# schematic.net
KiCad netlist of a schematic drawn in Altium Designer
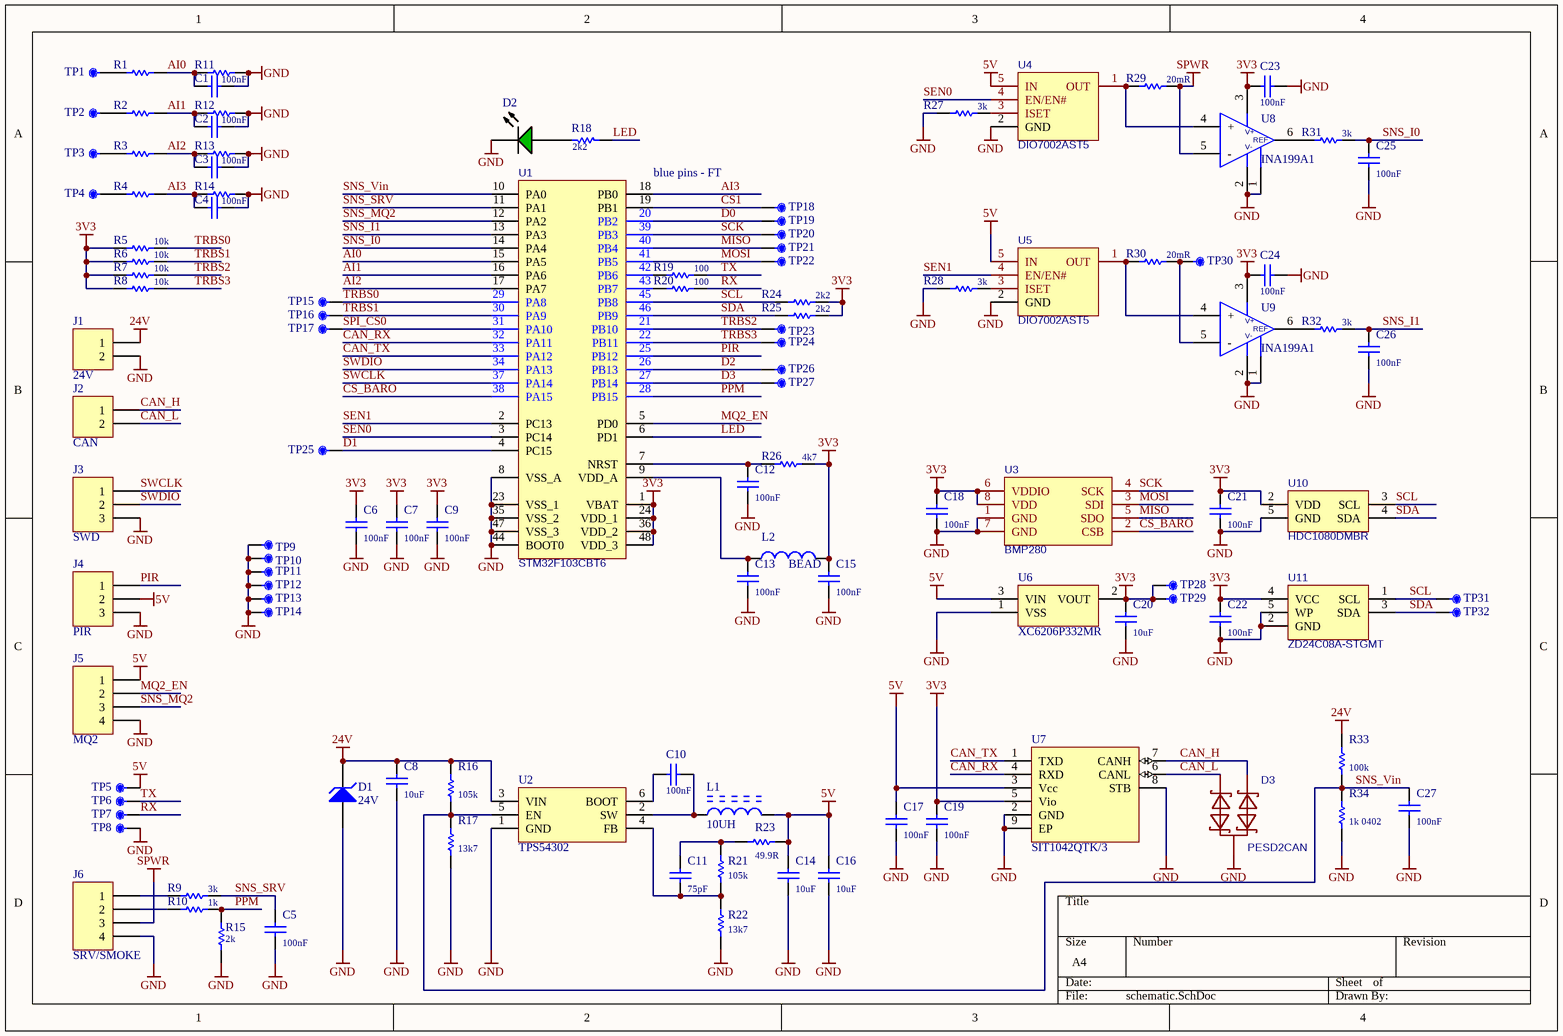
[diagram p0: schematic.SchDoc]

(export (version "E")
  (design (tool "Eeschema 10.0.6"))
  (components
    (comp (ref "C1")
      (value "100nF")
      (footprint "C0402")
      (description "100nF 50V 0402")
      (fields (field (name "LCSC PART NUMBER") "C110251"))
      (libsource (lib "Miscellaneous Devices") (part "CAP"))
    )
    (comp (ref "C2")
      (value "100nF")
      (footprint "C0402")
      (description "100nF 50V 0402")
      (fields (field (name "LCSC PART NUMBER") "C110251"))
      (libsource (lib "Miscellaneous Devices") (part "CAP"))
    )
    (comp (ref "C3")
      (value "100nF")
      (footprint "C0402")
      (description "100nF 50V 0402")
      (fields (field (name "LCSC PART NUMBER") "C110251"))
      (libsource (lib "Miscellaneous Devices") (part "CAP"))
    )
    (comp (ref "C4")
      (value "100nF")
      (footprint "C0402")
      (description "100nF 50V 0402")
      (fields (field (name "LCSC PART NUMBER") "C110251"))
      (libsource (lib "Miscellaneous Devices") (part "CAP"))
    )
    (comp (ref "C5")
      (value "100nF")
      (footprint "C0402")
      (description "100nF 50V 0402")
      (fields (field (name "LCSC PART NUMBER") "C110251"))
      (libsource (lib "Miscellaneous Devices") (part "CAP"))
    )
    (comp (ref "C6")
      (value "100nF")
      (footprint "C0402")
      (description "100nF 50V 0402")
      (fields (field (name "LCSC PART NUMBER") "C110251"))
      (libsource (lib "Miscellaneous Devices") (part "CAP"))
    )
    (comp (ref "C7")
      (value "100nF")
      (footprint "C0402")
      (description "100nF 50V 0402")
      (fields (field (name "LCSC PART NUMBER") "C110251"))
      (libsource (lib "Miscellaneous Devices") (part "CAP"))
    )
    (comp (ref "C8")
      (value "10uF")
      (footprint "C1206")
      (description "10uf 50V 1206")
      (fields (field (name "LCSC PART NUMBER") "C89632"))
      (libsource (lib "Miscellaneous Devices") (part "CAP"))
    )
    (comp (ref "C9")
      (value "100nF")
      (footprint "C0402")
      (description "100nF 50V 0402")
      (fields (field (name "LCSC PART NUMBER") "C110251"))
      (libsource (lib "Miscellaneous Devices") (part "CAP"))
    )
    (comp (ref "C10")
      (value "100nF")
      (footprint "C0402")
      (description "100nF 50V 0402")
      (fields (field (name "LCSC PART NUMBER") "C110251"))
      (libsource (lib "Miscellaneous Devices") (part "CAP"))
    )
    (comp (ref "C11")
      (value "75pF")
      (footprint "C0402")
      (description "75pF 50V 0402")
      (fields (field (name "LCSC PART NUMBER") "C107010"))
      (libsource (lib "Miscellaneous Devices") (part "CAP"))
    )
    (comp (ref "C12")
      (value "100nF")
      (footprint "C0402")
      (description "100nF 50V 0402")
      (fields (field (name "LCSC PART NUMBER") "C110251"))
      (libsource (lib "Miscellaneous Devices") (part "CAP"))
    )
    (comp (ref "C13")
      (value "100nF")
      (footprint "C0402")
      (description "100nF 50V 0402")
      (fields (field (name "LCSC PART NUMBER") "C110251"))
      (libsource (lib "Miscellaneous Devices") (part "CAP"))
    )
    (comp (ref "C14")
      (value "10uF")
      (footprint "C1206")
      (description "10uf 50V 1206")
      (fields (field (name "LCSC PART NUMBER") "C89632"))
      (libsource (lib "Miscellaneous Devices") (part "CAP"))
    )
    (comp (ref "C15")
      (value "100nF")
      (footprint "C0402")
      (description "100nF 50V 0402")
      (fields (field (name "LCSC PART NUMBER") "C110251"))
      (libsource (lib "Miscellaneous Devices") (part "CAP"))
    )
    (comp (ref "C16")
      (value "10uF")
      (footprint "C1206")
      (description "10uf 50V 1206")
      (fields (field (name "LCSC PART NUMBER") "C89632"))
      (libsource (lib "Miscellaneous Devices") (part "CAP"))
    )
    (comp (ref "C17")
      (value "100nF")
      (footprint "C0402")
      (description "100nF 50V 0402")
      (fields (field (name "LCSC PART NUMBER") "C110251"))
      (libsource (lib "Miscellaneous Devices") (part "CAP"))
    )
    (comp (ref "C18")
      (value "100nF")
      (footprint "C0402")
      (description "100nF 50V 0402")
      (fields (field (name "LCSC PART NUMBER") "C110251"))
      (libsource (lib "Miscellaneous Devices") (part "CAP"))
    )
    (comp (ref "C19")
      (value "100nF")
      (footprint "C0402")
      (description "100nF 50V 0402")
      (fields (field (name "LCSC PART NUMBER") "C110251"))
      (libsource (lib "Miscellaneous Devices") (part "CAP"))
    )
    (comp (ref "C20")
      (value "10uF")
      (footprint "C1206")
      (description "10uf 50V 1206")
      (fields (field (name "LCSC PART NUMBER") "C89632"))
      (libsource (lib "Miscellaneous Devices") (part "CAP"))
    )
    (comp (ref "C21")
      (value "100nF")
      (footprint "C0402")
      (description "100nF 50V 0402")
      (fields (field (name "LCSC PART NUMBER") "C110251"))
      (libsource (lib "Miscellaneous Devices") (part "CAP"))
    )
    (comp (ref "C22")
      (value "100nF")
      (footprint "C0402")
      (description "100nF 50V 0402")
      (fields (field (name "LCSC PART NUMBER") "C110251"))
      (libsource (lib "Miscellaneous Devices") (part "CAP"))
    )
    (comp (ref "C23")
      (value "100nF")
      (footprint "C0402")
      (description "100nF 50V 0402")
      (fields (field (name "LCSC PART NUMBER") "C110251"))
      (libsource (lib "Miscellaneous Devices") (part "CAP"))
    )
    (comp (ref "C24")
      (value "100nF")
      (footprint "C0402")
      (description "100nF 50V 0402")
      (fields (field (name "LCSC PART NUMBER") "C110251"))
      (libsource (lib "Miscellaneous Devices") (part "CAP"))
    )
    (comp (ref "C25")
      (value "100nF")
      (footprint "C0402")
      (description "100nF 50V 0402")
      (fields (field (name "LCSC PART NUMBER") "C110251"))
      (libsource (lib "Miscellaneous Devices") (part "CAP"))
    )
    (comp (ref "C26")
      (value "100nF")
      (footprint "C0402")
      (description "100nF 50V 0402")
      (fields (field (name "LCSC PART NUMBER") "C110251"))
      (libsource (lib "Miscellaneous Devices") (part "CAP"))
    )
    (comp (ref "C27")
      (value "100nF")
      (footprint "C0402")
      (description "100nF 50V 0402")
      (fields (field (name "LCSC PART NUMBER") "C110251"))
      (libsource (lib "Miscellaneous Devices") (part "CAP"))
    )
    (comp (ref "D1")
      (value "24V")
      (footprint "SMB")
      (description "P6SMB24A")
      (fields (field (name "LCSC PART NUMBER") "C5155417"))
      (libsource (lib "Miscellaneous Devices") (part "SMCJ54A"))
    )
    (comp (ref "D2")
      (value "GRN")
      (footprint "LED-0603-GRN")
      (description "LED 0603 GRN")
      (fields (field (name "LCSC PART NUMBER") "C434446"))
      (libsource (lib "Miscellaneous Devices") (part "LED-0603-GREEN"))
    )
    (comp (ref "D3")
      (value "PESD2CAN")
      (footprint "SOT-23")
      (fields (field (name "LCSC PART NUMBER") "C5261081"))
      (libsource (lib "Miscellaneous Devices") (part "CDSOT23-SM712"))
    )
    (comp (ref "J1")
      (value "24V")
      (footprint "CONN_DG308-2.54-2P")
      (description "DG308-2.54-02P-14-00A(H)")
      (fields (field (name "LCSC PART NUMBER") "C699496"))
      (libsource (lib "Miscellaneous Devices") (part "CONN MOLEX HDR-M 1x4"))
    )
    (comp (ref "J2")
      (value "CAN")
      (footprint "CONN_DG308-2.54-2P")
      (description "DG308-2.54-02P-14-00A(H)")
      (fields (field (name "LCSC PART NUMBER") "C699496"))
      (libsource (lib "Miscellaneous Devices") (part "CONN MOLEX HDR-M 1x4"))
    )
    (comp (ref "J3")
      (value "SWD")
      (footprint "SWD")
      (libsource (lib "Miscellaneous Devices") (part "Header 3"))
    )
    (comp (ref "J4")
      (value "PIR")
      (footprint "CONN_MOLEX_532610371")
      (libsource (lib "Miscellaneous Devices") (part "Header 3"))
    )
    (comp (ref "J5")
      (value "MQ2")
      (footprint "CONN_MOLEX_532610471")
      (libsource (lib "Schlib1") (part "Header 3"))
    )
    (comp (ref "J6") (value "SRV/SMOKE") (footprint "HDR-1X4") (libsource (lib "Schlib1") (part "Header 3")))
    (comp (ref "L1")
      (value "10UH")
      (footprint "IND-SMD_L7.2-W6.6_GPSR07X0")
      (description "CYA0630-10UH")
      (fields (field (name "LCSC PART NUMBER") "C5189958"))
      (libsource (lib "Miscellaneous Devices") (part "SRN3015-100M"))
    )
    (comp (ref "L2")
      (value "BEAD")
      (footprint "L0402")
      (description "BEAD 0402")
      (fields (field (name "LCSC PART NUMBER") "C76883"))
      (libsource (lib "Miscellaneous Devices") (part "BLM18AG601SN1D"))
    )
    (comp (ref "R1")
      (value "10k")
      (footprint "R0402")
      (description "10k 0402")
      (fields (field (name "LCSC PART NUMBER") "C25744"))
      (libsource (lib "Miscellaneous Devices") (part "RES"))
    )
    (comp (ref "R2")
      (value "10k")
      (footprint "R0402")
      (description "10k 0402")
      (fields (field (name "LCSC PART NUMBER") "C25744"))
      (libsource (lib "Miscellaneous Devices") (part "RES"))
    )
    (comp (ref "R3")
      (value "10k")
      (footprint "R0402")
      (description "10k 0402")
      (fields (field (name "LCSC PART NUMBER") "C25744"))
      (libsource (lib "Miscellaneous Devices") (part "RES"))
    )
    (comp (ref "R4")
      (value "10k")
      (footprint "R0402")
      (description "10k 0402")
      (fields (field (name "LCSC PART NUMBER") "C25744"))
      (libsource (lib "Miscellaneous Devices") (part "RES"))
    )
    (comp (ref "R5")
      (value "10k")
      (footprint "R0402")
      (description "10k 0402")
      (fields (field (name "LCSC PART NUMBER") "C25744"))
      (libsource (lib "Miscellaneous Devices") (part "RES"))
    )
    (comp (ref "R6")
      (value "10k")
      (footprint "R0402")
      (description "10k 0402")
      (fields (field (name "LCSC PART NUMBER") "C25744"))
      (libsource (lib "Miscellaneous Devices") (part "RES"))
    )
    (comp (ref "R7")
      (value "10k")
      (footprint "R0402")
      (description "10k 0402")
      (fields (field (name "LCSC PART NUMBER") "C25744"))
      (libsource (lib "Miscellaneous Devices") (part "RES"))
    )
    (comp (ref "R8")
      (value "10k")
      (footprint "R0402")
      (description "10k 0402")
      (fields (field (name "LCSC PART NUMBER") "C25744"))
      (libsource (lib "Miscellaneous Devices") (part "RES"))
    )
    (comp (ref "R9")
      (value "3k")
      (footprint "R0402")
      (description "3k 0402")
      (fields (field (name "LCSC PART NUMBER") "C25784"))
      (libsource (lib "") (part "RES_1"))
    )
    (comp (ref "R10")
      (value "1k")
      (footprint "R0402")
      (description "1k 0402")
      (fields (field (name "LCSC PART NUMBER") "C11702"))
      (libsource (lib "Miscellaneous Devices") (part "RES"))
    )
    (comp (ref "R11")
      (value "20k")
      (footprint "R0402")
      (description "20k 0402")
      (fields (field (name "LCSC PART NUMBER") "C25765"))
      (libsource (lib "Miscellaneous Devices") (part "RES"))
    )
    (comp (ref "R12")
      (value "20k")
      (footprint "R0402")
      (description "20k 0402")
      (fields (field (name "LCSC PART NUMBER") "C25765"))
      (libsource (lib "Miscellaneous Devices") (part "RES"))
    )
    (comp (ref "R13")
      (value "20k")
      (footprint "R0402")
      (description "20k 0402")
      (fields (field (name "LCSC PART NUMBER") "C25765"))
      (libsource (lib "Miscellaneous Devices") (part "RES"))
    )
    (comp (ref "R14")
      (value "20k")
      (footprint "R0402")
      (description "20k 0402")
      (fields (field (name "LCSC PART NUMBER") "C25765"))
      (libsource (lib "Miscellaneous Devices") (part "RES"))
    )
    (comp (ref "R15")
      (value "2k")
      (footprint "R0402")
      (description "2k 0402")
      (fields (field (name "LCSC PART NUMBER") "C4109"))
      (libsource (lib "Miscellaneous Devices") (part "RES"))
    )
    (comp (ref "R16")
      (value "105k")
      (footprint "R0402")
      (description "105k 0402")
      (fields (field (name "LCSC PART NUMBER") "C170210"))
      (libsource (lib "Miscellaneous Devices") (part "RES"))
    )
    (comp (ref "R17")
      (value "13k7")
      (footprint "R0402")
      (description "13k7 0402")
      (fields (field (name "LCSC PART NUMBER") "C2933072"))
      (libsource (lib "Miscellaneous Devices") (part "RES"))
    )
    (comp (ref "R18")
      (value "2k2")
      (footprint "R0402")
      (description "2k 0402")
      (fields (field (name "LCSC PART NUMBER") "C4109"))
      (libsource (lib "Miscellaneous Devices") (part "RES"))
    )
    (comp (ref "R19")
      (value "100")
      (footprint "R0402")
      (description "100 0402")
      (fields (field (name "LCSC PART NUMBER") "C25076"))
      (libsource (lib "Miscellaneous Devices") (part "RES"))
    )
    (comp (ref "R20")
      (value "100")
      (footprint "R0402")
      (description "100 0402")
      (fields (field (name "LCSC PART NUMBER") "C25076"))
      (libsource (lib "Miscellaneous Devices") (part "RES"))
    )
    (comp (ref "R21")
      (value "105k")
      (footprint "R0402")
      (description "105k 0402")
      (fields (field (name "LCSC PART NUMBER") "C170210"))
      (libsource (lib "Miscellaneous Devices") (part "RES"))
    )
    (comp (ref "R22")
      (value "13k7")
      (footprint "R0402")
      (description "13k7 0402")
      (fields (field (name "LCSC PART NUMBER") "C2933072"))
      (libsource (lib "Miscellaneous Devices") (part "RES"))
    )
    (comp (ref "R23")
      (value "49.9R")
      (footprint "R0402")
      (description "49R9 0402")
      (fields (field (name "LCSC PART NUMBER") "C87044"))
      (libsource (lib "") (part "RES_2"))
    )
    (comp (ref "R24")
      (value "2k2")
      (footprint "R0402")
      (description "2k 0402")
      (fields (field (name "LCSC PART NUMBER") "C4109"))
      (libsource (lib "Miscellaneous Devices") (part "RES"))
    )
    (comp (ref "R25")
      (value "2k2")
      (footprint "R0402")
      (description "2k 0402")
      (fields (field (name "LCSC PART NUMBER") "C4109"))
      (libsource (lib "Miscellaneous Devices") (part "RES"))
    )
    (comp (ref "R26")
      (value "4k7")
      (footprint "R0402")
      (description "4k7 0402")
      (fields (field (name "LCSC PART NUMBER") "C25900"))
      (libsource (lib "Miscellaneous Devices") (part "RES"))
    )
    (comp (ref "R27")
      (value "3k")
      (footprint "R0402")
      (description "3k 0402")
      (fields (field (name "LCSC PART NUMBER") "C25784"))
      (libsource (lib "") (part "RES_1"))
    )
    (comp (ref "R28")
      (value "3k")
      (footprint "R0402")
      (description "3k 0402")
      (fields (field (name "LCSC PART NUMBER") "C25784"))
      (libsource (lib "") (part "RES_1"))
    )
    (comp (ref "R29")
      (value "20mR")
      (footprint "R0805")
      (description "0805W4F200MT5E")
      (fields (field (name "LCSC PART NUMBER") "C7467520"))
      (libsource (lib "") (part "RES_1"))
    )
    (comp (ref "R30")
      (value "20mR")
      (footprint "R0805")
      (description "0805W4F200MT5E")
      (fields (field (name "LCSC PART NUMBER") "C7467520"))
      (libsource (lib "") (part "RES_1"))
    )
    (comp (ref "R31")
      (value "3k")
      (footprint "R0402")
      (description "3k 0402")
      (fields (field (name "LCSC PART NUMBER") "C25784"))
      (libsource (lib "Miscellaneous Devices") (part "RES"))
    )
    (comp (ref "R32")
      (value "3k")
      (footprint "R0402")
      (description "3k 0402")
      (fields (field (name "LCSC PART NUMBER") "C25784"))
      (libsource (lib "Miscellaneous Devices") (part "RES"))
    )
    (comp (ref "R33")
      (value "100k")
      (footprint "R0402")
      (description "100k 0402")
      (fields (field (name "LCSC PART NUMBER") "C60491"))
      (libsource (lib "Miscellaneous Devices") (part "RES"))
    )
    (comp (ref "R34")
      (value "1k 0402")
      (footprint "R0402")
      (description "10k 0402")
      (fields (field (name "LCSC PART NUMBER") "C25744"))
      (libsource (lib "Miscellaneous Devices") (part "RES"))
    )
    (comp (ref "TP1")
      (value "~")
      (footprint "TP_TH_S0")
      (libsource (lib "Miscellaneous Devices") (part "TP_Dup1"))
    )
    (comp (ref "TP2")
      (value "~")
      (footprint "TP_TH_S0")
      (libsource (lib "Miscellaneous Devices") (part "TP_Dup1"))
    )
    (comp (ref "TP3")
      (value "~")
      (footprint "TP_TH_S0")
      (libsource (lib "Miscellaneous Devices") (part "TP_Dup1"))
    )
    (comp (ref "TP4")
      (value "~")
      (footprint "TP_TH_S0")
      (libsource (lib "Miscellaneous Devices") (part "TP_Dup1"))
    )
    (comp (ref "TP5")
      (value "~")
      (footprint "TP_TH_S0")
      (libsource (lib "Miscellaneous Devices") (part "TP_Dup1"))
    )
    (comp (ref "TP6")
      (value "~")
      (footprint "TP_TH_S0")
      (libsource (lib "Miscellaneous Devices") (part "TP_Dup1"))
    )
    (comp (ref "TP7")
      (value "~")
      (footprint "TP_TH_S0")
      (libsource (lib "Miscellaneous Devices") (part "TP_Dup1"))
    )
    (comp (ref "TP8")
      (value "~")
      (footprint "TP_TH_S0")
      (libsource (lib "Miscellaneous Devices") (part "TP_Dup1"))
    )
    (comp (ref "TP9")
      (value "~")
      (footprint "TP_TH_S0")
      (libsource (lib "Miscellaneous Devices") (part "TP_Dup1"))
    )
    (comp (ref "TP10")
      (value "~")
      (footprint "TP_TH_S0")
      (libsource (lib "Miscellaneous Devices") (part "TP_Dup1"))
    )
    (comp (ref "TP11")
      (value "~")
      (footprint "TP_TH_S0")
      (libsource (lib "Miscellaneous Devices") (part "TP_Dup1"))
    )
    (comp (ref "TP12")
      (value "~")
      (footprint "TP_TH_S0")
      (libsource (lib "Miscellaneous Devices") (part "TP_Dup1"))
    )
    (comp (ref "TP13")
      (value "~")
      (footprint "TP_TH_S0")
      (libsource (lib "Miscellaneous Devices") (part "TP_Dup1"))
    )
    (comp (ref "TP14")
      (value "~")
      (footprint "TP_TH_S0")
      (libsource (lib "Miscellaneous Devices") (part "TP_Dup1"))
    )
    (comp (ref "TP15")
      (value "~")
      (footprint "TP_TH_S0")
      (libsource (lib "Miscellaneous Devices") (part "TP_Dup1"))
    )
    (comp (ref "TP16")
      (value "~")
      (footprint "TP_TH_S0")
      (libsource (lib "Miscellaneous Devices") (part "TP_Dup1"))
    )
    (comp (ref "TP17")
      (value "~")
      (footprint "TP_TH_S0")
      (libsource (lib "Miscellaneous Devices") (part "TP_Dup1"))
    )
    (comp (ref "TP18")
      (value "~")
      (footprint "TP_TH_S0")
      (libsource (lib "Miscellaneous Devices") (part "TP_Dup1"))
    )
    (comp (ref "TP19")
      (value "~")
      (footprint "TP_TH_S0")
      (libsource (lib "Miscellaneous Devices") (part "TP_Dup1"))
    )
    (comp (ref "TP20")
      (value "~")
      (footprint "TP_TH_S0")
      (libsource (lib "Miscellaneous Devices") (part "TP_Dup1"))
    )
    (comp (ref "TP21")
      (value "~")
      (footprint "TP_TH_S0")
      (libsource (lib "Miscellaneous Devices") (part "TP_Dup1"))
    )
    (comp (ref "TP22")
      (value "~")
      (footprint "TP_TH_S0")
      (libsource (lib "Miscellaneous Devices") (part "TP_Dup1"))
    )
    (comp (ref "TP23")
      (value "~")
      (footprint "TP_TH_S0")
      (libsource (lib "Miscellaneous Devices") (part "TP_Dup1"))
    )
    (comp (ref "TP24")
      (value "~")
      (footprint "TP_TH_S0")
      (libsource (lib "Miscellaneous Devices") (part "TP_Dup1"))
    )
    (comp (ref "TP25")
      (value "~")
      (footprint "TP_TH_S0")
      (libsource (lib "Miscellaneous Devices") (part "TP_Dup1"))
    )
    (comp (ref "TP26")
      (value "~")
      (footprint "TP_TH_S0")
      (libsource (lib "Miscellaneous Devices") (part "TP_Dup1"))
    )
    (comp (ref "TP27")
      (value "~")
      (footprint "TP_TH_S0")
      (libsource (lib "Miscellaneous Devices") (part "TP_Dup1"))
    )
    (comp (ref "TP28")
      (value "~")
      (footprint "TP_TH_S0")
      (libsource (lib "Miscellaneous Devices") (part "TP_Dup1"))
    )
    (comp (ref "TP29")
      (value "~")
      (footprint "TP_TH_S0")
      (libsource (lib "Miscellaneous Devices") (part "TP_Dup1"))
    )
    (comp (ref "TP30")
      (value "~")
      (footprint "TP_TH_S0")
      (libsource (lib "Miscellaneous Devices") (part "TP_Dup1"))
    )
    (comp (ref "TP31")
      (value "~")
      (footprint "TP_TH_S0")
      (libsource (lib "Miscellaneous Devices") (part "TP_Dup1"))
    )
    (comp (ref "TP32")
      (value "~")
      (footprint "TP_TH_S0")
      (libsource (lib "Miscellaneous Devices") (part "TP_Dup1"))
    )
    (comp (ref "U1")
      (value "STM32F103CBT6")
      (footprint "LQFP-48")
      (fields (field (name "LCSC PART NUMBER") "C8304"))
      (libsource (lib "Schlib1") (part "STM32F103CBT6"))
    )
    (comp (ref "U2")
      (value "TPS54302")
      (footprint "SOT-23-6")
      (description "TPS54302DDCR")
      (fields (field (name "LCSC PART NUMBER") "C311983"))
      (libsource (lib "Miscellaneous Devices") (part "LM27313XMFX"))
    )
    (comp (ref "U3")
      (value "BMP280")
      (footprint "WLGA-8_L2.5-W2.0-P0.65-TR_DPS422")
      (fields (field (name "LCSC PART NUMBER") "C83291"))
      (libsource (lib "Schlib1") (part "BMP280"))
    )
    (comp (ref "U4")
      (value "DIO7002AST5")
      (footprint "SOT-23-5")
      (fields (field (name "LCSC PART NUMBER") "C403840"))
      (libsource (lib "Schlib1") (part "DIO7002AST5"))
    )
    (comp (ref "U5")
      (value "DIO7002AST5")
      (footprint "SOT-23-5")
      (fields (field (name "LCSC PART NUMBER") "C403840"))
      (libsource (lib "Schlib1") (part "DIO7002AST5"))
    )
    (comp (ref "U6")
      (value "XC6206P332MR")
      (footprint "SOT-23")
      (fields (field (name "LCSC PART NUMBER") "C5148692"))
      (libsource (lib "Schlib1") (part "Component_4_1"))
    )
    (comp (ref "U7")
      (value "SIT1042QTK/3")
      (footprint "DFN8_3X3_P065")
      (description "IC INTERFACE CAN")
      (fields (field (name "LCSC PART NUMBER") "C5308062"))
      (libsource (lib "Miscellaneous Devices") (part "LTC2875"))
    )
    (comp (ref "U8")
      (value "INA199A1")
      (footprint "SOT-363")
      (fields (field (name "LCSC PART NUMBER") "C59135"))
      (libsource (lib "Miscellaneous Devices") (part "MCP65R41T-2402"))
    )
    (comp (ref "U9")
      (value "INA199A1")
      (footprint "SOT-363")
      (fields (field (name "LCSC PART NUMBER") "C59135"))
      (libsource (lib "Miscellaneous Devices") (part "MCP65R41T-2402"))
    )
    (comp (ref "U10")
      (value "HDC1080DMBR")
      (footprint "SENSOR-SMD_L3.0-W3.0-P1.00-BR")
      (fields (field (name "LCSC PART NUMBER") "C82227"))
      (libsource (lib "Schlib1") (part "AHT21"))
    )
    (comp (ref "U11")
      (value "ZD24C08A-STGMT")
      (footprint "SOT-23-5")
      (fields (field (name "LCSC PART NUMBER") "C2896640"))
      (libsource (lib "Schlib1") (part "ZD24C08A-STGMT"))
    )
  )
  (nets
    (net (code "1") (name "/AI0") (class "Default")
      (node (ref "C1") (pin "2") (pinfunction "2_2") (pintype "passive"))
      (node (ref "R1") (pin "1") (pinfunction "1_1") (pintype "passive"))
      (node (ref "R11") (pin "2") (pinfunction "2_2") (pintype "passive"))
      (node (ref "U1") (pin "15") (pinfunction "PA5_15") (pintype "passive"))
    )
    (net (code "2") (name "/AI1") (class "Default")
      (node (ref "C2") (pin "2") (pinfunction "2_2") (pintype "passive"))
      (node (ref "R12") (pin "2") (pinfunction "2_2") (pintype "passive"))
      (node (ref "R2") (pin "1") (pinfunction "1_1") (pintype "passive"))
      (node (ref "U1") (pin "16") (pinfunction "PA6_16") (pintype "passive"))
    )
    (net (code "3") (name "/AI2") (class "Default")
      (node (ref "C3") (pin "2") (pinfunction "2_2") (pintype "passive"))
      (node (ref "R13") (pin "2") (pinfunction "2_2") (pintype "passive"))
      (node (ref "R3") (pin "1") (pinfunction "1_1") (pintype "passive"))
      (node (ref "U1") (pin "17") (pinfunction "PA7_17") (pintype "passive"))
    )
    (net (code "4") (name "/AI3") (class "Default")
      (node (ref "C4") (pin "2") (pinfunction "2_2") (pintype "passive"))
      (node (ref "R14") (pin "2") (pinfunction "2_2") (pintype "passive"))
      (node (ref "R4") (pin "1") (pinfunction "1_1") (pintype "passive"))
      (node (ref "U1") (pin "18") (pinfunction "PB0_18") (pintype "passive"))
    )
    (net (code "5") (name "/CAN_H") (class "Default")
      (node (ref "D3") (pin "2") (pinfunction "2_2") (pintype "passive"))
      (node (ref "J2") (pin "1") (pinfunction "1_1") (pintype "passive"))
      (node (ref "U7") (pin "7") (pinfunction "CANH_7") (pintype "bidirectional"))
    )
    (net (code "6") (name "/CAN_L") (class "Default")
      (node (ref "D3") (pin "1") (pinfunction "1_1") (pintype "passive"))
      (node (ref "J2") (pin "2") (pinfunction "2_2") (pintype "passive"))
      (node (ref "U7") (pin "6") (pinfunction "CANL_6") (pintype "bidirectional"))
    )
    (net (code "7") (name "/CAN_RX") (class "Default")
      (node (ref "U1") (pin "32") (pinfunction "PA11_32") (pintype "passive"))
      (node (ref "U7") (pin "4") (pinfunction "RXD_4") (pintype "passive"))
    )
    (net (code "8") (name "/CAN_TX") (class "Default")
      (node (ref "U1") (pin "33") (pinfunction "PA12_33") (pintype "passive"))
      (node (ref "U7") (pin "1") (pinfunction "TXD_1") (pintype "passive"))
    )
    (net (code "9") (name "/CS1") (class "Default")
      (node (ref "TP18") (pin "1") (pinfunction "1_1") (pintype "passive"))
      (node (ref "U1") (pin "19") (pinfunction "PB1_19") (pintype "passive"))
    )
    (net (code "10") (name "/CS_BARO") (class "Default")
      (node (ref "U1") (pin "38") (pinfunction "PA15_38") (pintype "passive"))
      (node (ref "U3") (pin "2") (pinfunction "CSB_2") (pintype "passive"))
    )
    (net (code "11") (name "/D0") (class "Default")
      (node (ref "TP19") (pin "1") (pinfunction "1_1") (pintype "passive"))
      (node (ref "U1") (pin "20") (pinfunction "PB2_20") (pintype "passive"))
    )
    (net (code "12") (name "/D1") (class "Default")
      (node (ref "TP25") (pin "1") (pinfunction "1_1") (pintype "passive"))
      (node (ref "U1") (pin "4") (pinfunction "PC15_4") (pintype "passive"))
    )
    (net (code "13") (name "/D2") (class "Default")
      (node (ref "TP26") (pin "1") (pinfunction "1_1") (pintype "passive"))
      (node (ref "U1") (pin "26") (pinfunction "PB13_26") (pintype "passive"))
    )
    (net (code "14") (name "/D3") (class "Default")
      (node (ref "TP27") (pin "1") (pinfunction "1_1") (pintype "passive"))
      (node (ref "U1") (pin "27") (pinfunction "PB14_27") (pintype "passive"))
    )
    (net (code "15") (name "/LED") (class "Default")
      (node (ref "R18") (pin "2") (pinfunction "2_2") (pintype "passive"))
      (node (ref "U1") (pin "6") (pinfunction "PD1_6") (pintype "passive"))
    )
    (net (code "16") (name "/MISO") (class "Default")
      (node (ref "TP21") (pin "1") (pinfunction "1_1") (pintype "passive"))
      (node (ref "U1") (pin "40") (pinfunction "PB4_40") (pintype "passive"))
      (node (ref "U3") (pin "5") (pinfunction "SDO_5") (pintype "passive"))
    )
    (net (code "17") (name "/MOSI") (class "Default")
      (node (ref "TP22") (pin "1") (pinfunction "1_1") (pintype "passive"))
      (node (ref "U1") (pin "41") (pinfunction "PB5_41") (pintype "passive"))
      (node (ref "U3") (pin "3") (pinfunction "SDI_3") (pintype "passive"))
    )
    (net (code "18") (name "/MQ2_EN") (class "Default")
      (node (ref "J5") (pin "2") (pinfunction "2_2") (pintype "passive"))
      (node (ref "U1") (pin "5") (pinfunction "PD0_5") (pintype "passive"))
    )
    (net (code "19") (name "/PIR") (class "Default")
      (node (ref "J4") (pin "1") (pinfunction "1_1") (pintype "passive"))
      (node (ref "U1") (pin "25") (pinfunction "PB12_25") (pintype "passive"))
    )
    (net (code "20") (name "/PPM") (class "Default")
      (node (ref "R10") (pin "1") (pinfunction "1_1") (pintype "passive"))
      (node (ref "R15") (pin "1") (pinfunction "1_1") (pintype "passive"))
      (node (ref "U1") (pin "28") (pinfunction "PB15_28") (pintype "passive"))
    )
    (net (code "21") (name "/RX") (class "Default")
      (node (ref "R20") (pin "1") (pinfunction "1_1") (pintype "passive"))
      (node (ref "TP7") (pin "1") (pinfunction "1_1") (pintype "passive"))
    )
    (net (code "22") (name "/SCK") (class "Default")
      (node (ref "TP20") (pin "1") (pinfunction "1_1") (pintype "passive"))
      (node (ref "U1") (pin "39") (pinfunction "PB3_39") (pintype "passive"))
      (node (ref "U3") (pin "4") (pinfunction "SCK_4") (pintype "passive"))
    )
    (net (code "23") (name "/SCL") (class "Default")
      (node (ref "R24") (pin "1") (pinfunction "1_1") (pintype "passive"))
      (node (ref "TP31") (pin "1") (pinfunction "1_1") (pintype "passive"))
      (node (ref "U1") (pin "45") (pinfunction "PB8_45") (pintype "passive"))
      (node (ref "U10") (pin "3") (pinfunction "SCL_3") (pintype "passive"))
      (node (ref "U11") (pin "1") (pinfunction "SCL_1") (pintype "passive"))
    )
    (net (code "24") (name "/SDA") (class "Default")
      (node (ref "R25") (pin "1") (pinfunction "1_1") (pintype "passive"))
      (node (ref "TP32") (pin "1") (pinfunction "1_1") (pintype "passive"))
      (node (ref "U1") (pin "46") (pinfunction "PB9_46") (pintype "passive"))
      (node (ref "U10") (pin "4") (pinfunction "SDA_4") (pintype "passive"))
      (node (ref "U11") (pin "3") (pinfunction "SDA_3") (pintype "passive"))
    )
    (net (code "25") (name "/SEN0") (class "Default")
      (node (ref "U1") (pin "3") (pinfunction "PC14_3") (pintype "passive"))
      (node (ref "U4") (pin "4") (pinfunction "EN/EN#_4") (pintype "passive"))
    )
    (net (code "26") (name "/SEN1") (class "Default")
      (node (ref "U1") (pin "2") (pinfunction "PC13_2") (pintype "passive"))
      (node (ref "U5") (pin "4") (pinfunction "EN/EN#_4") (pintype "passive"))
    )
    (net (code "27") (name "/SNS_I0") (class "Default")
      (node (ref "C25") (pin "2") (pinfunction "2_2") (pintype "passive"))
      (node (ref "R31") (pin "1") (pinfunction "1_1") (pintype "passive"))
      (node (ref "U1") (pin "14") (pinfunction "PA4_14") (pintype "passive"))
    )
    (net (code "28") (name "/SNS_I1") (class "Default")
      (node (ref "C26") (pin "2") (pinfunction "2_2") (pintype "passive"))
      (node (ref "R32") (pin "1") (pinfunction "1_1") (pintype "passive"))
      (node (ref "U1") (pin "13") (pinfunction "PA3_13") (pintype "passive"))
    )
    (net (code "29") (name "/SNS_MQ2") (class "Default")
      (node (ref "J5") (pin "3") (pinfunction "3_3") (pintype "passive"))
      (node (ref "U1") (pin "12") (pinfunction "PA2_12") (pintype "passive"))
    )
    (net (code "30") (name "/SNS_SRV") (class "Default")
      (node (ref "C5") (pin "2") (pinfunction "2_2") (pintype "passive"))
      (node (ref "R9") (pin "1") (pinfunction "1_1") (pintype "passive"))
      (node (ref "U1") (pin "11") (pinfunction "PA1_11") (pintype "passive"))
    )
    (net (code "31") (name "/SNS_Vin") (class "Default")
      (node (ref "C27") (pin "2") (pinfunction "2_2") (pintype "passive"))
      (node (ref "R16") (pin "2") (pinfunction "2_2") (pintype "passive"))
      (node (ref "R17") (pin "1") (pinfunction "1_1") (pintype "passive"))
      (node (ref "R33") (pin "2") (pinfunction "2_2") (pintype "passive"))
      (node (ref "R34") (pin "1") (pinfunction "1_1") (pintype "passive"))
      (node (ref "U1") (pin "10") (pinfunction "PA0_10") (pintype "passive"))
      (node (ref "U2") (pin "5") (pinfunction "EN_5") (pintype "passive"))
    )
    (net (code "32") (name "/SPI_CS0") (class "Default")
      (node (ref "TP17") (pin "1") (pinfunction "1_1") (pintype "passive"))
      (node (ref "U1") (pin "31") (pinfunction "PA10_31") (pintype "passive"))
    )
    (net (code "33") (name "/SWCLK") (class "Default")
      (node (ref "J3") (pin "1") (pinfunction "1_1") (pintype "passive"))
      (node (ref "U1") (pin "37") (pinfunction "PA14_37") (pintype "passive"))
    )
    (net (code "34") (name "/SWDIO") (class "Default")
      (node (ref "J3") (pin "2") (pinfunction "2_2") (pintype "passive"))
      (node (ref "U1") (pin "34") (pinfunction "PA13_34") (pintype "passive"))
    )
    (net (code "35") (name "/TRBS0") (class "Default")
      (node (ref "R5") (pin "1") (pinfunction "1_1") (pintype "passive"))
      (node (ref "TP15") (pin "1") (pinfunction "1_1") (pintype "passive"))
      (node (ref "U1") (pin "29") (pinfunction "PA8_29") (pintype "passive"))
    )
    (net (code "36") (name "/TRBS1") (class "Default")
      (node (ref "R6") (pin "1") (pinfunction "1_1") (pintype "passive"))
      (node (ref "TP16") (pin "1") (pinfunction "1_1") (pintype "passive"))
      (node (ref "U1") (pin "30") (pinfunction "PA9_30") (pintype "passive"))
    )
    (net (code "37") (name "/TRBS2") (class "Default")
      (node (ref "R7") (pin "1") (pinfunction "1_1") (pintype "passive"))
      (node (ref "TP23") (pin "1") (pinfunction "1_1") (pintype "passive"))
      (node (ref "U1") (pin "21") (pinfunction "PB10_21") (pintype "passive"))
    )
    (net (code "38") (name "/TRBS3") (class "Default")
      (node (ref "R8") (pin "1") (pinfunction "1_1") (pintype "passive"))
      (node (ref "TP24") (pin "1") (pinfunction "1_1") (pintype "passive"))
      (node (ref "U1") (pin "22") (pinfunction "PB11_22") (pintype "passive"))
    )
    (net (code "39") (name "/TX") (class "Default")
      (node (ref "R19") (pin "1") (pinfunction "1_1") (pintype "passive"))
      (node (ref "TP6") (pin "1") (pinfunction "1_1") (pintype "passive"))
    )
    (net (code "40") (name "3V3") (class "Default")
      (node (ref "C15") (pin "2") (pinfunction "2_2") (pintype "passive"))
      (node (ref "C18") (pin "2") (pinfunction "2_2") (pintype "passive"))
      (node (ref "C19") (pin "2") (pinfunction "2_2") (pintype "passive"))
      (node (ref "C20") (pin "2") (pinfunction "2_2") (pintype "passive"))
      (node (ref "C21") (pin "2") (pinfunction "2_2") (pintype "passive"))
      (node (ref "C22") (pin "2") (pinfunction "2_2") (pintype "passive"))
      (node (ref "C23") (pin "2") (pinfunction "2_2") (pintype "passive"))
      (node (ref "C24") (pin "2") (pinfunction "2_2") (pintype "passive"))
      (node (ref "C6") (pin "2") (pinfunction "2_2") (pintype "passive"))
      (node (ref "C7") (pin "2") (pinfunction "2_2") (pintype "passive"))
      (node (ref "C9") (pin "2") (pinfunction "2_2") (pintype "passive"))
      (node (ref "L2") (pin "1") (pinfunction "1_1") (pintype "passive"))
      (node (ref "R24") (pin "2") (pinfunction "2_2") (pintype "passive"))
      (node (ref "R25") (pin "2") (pinfunction "2_2") (pintype "passive"))
      (node (ref "R26") (pin "1") (pinfunction "1_1") (pintype "passive"))
      (node (ref "R5") (pin "2") (pinfunction "2_2") (pintype "passive"))
      (node (ref "R6") (pin "2") (pinfunction "2_2") (pintype "passive"))
      (node (ref "R7") (pin "2") (pinfunction "2_2") (pintype "passive"))
      (node (ref "R8") (pin "2") (pinfunction "2_2") (pintype "passive"))
      (node (ref "TP28") (pin "1") (pinfunction "1_1") (pintype "passive"))
      (node (ref "TP29") (pin "1") (pinfunction "1_1") (pintype "passive"))
      (node (ref "U1") (pin "1") (pinfunction "VBAT_1") (pintype "passive"))
      (node (ref "U1") (pin "24") (pinfunction "VDD_1_24") (pintype "passive"))
      (node (ref "U1") (pin "36") (pinfunction "VDD_2_36") (pintype "passive"))
      (node (ref "U1") (pin "48") (pinfunction "VDD_3_48") (pintype "passive"))
      (node (ref "U10") (pin "2") (pinfunction "VDD_2") (pintype "passive"))
      (node (ref "U11") (pin "4") (pinfunction "VCC_4") (pintype "passive"))
      (node (ref "U3") (pin "6") (pinfunction "VDDIO_6") (pintype "passive"))
      (node (ref "U3") (pin "8") (pinfunction "VDD_8") (pintype "passive"))
      (node (ref "U6") (pin "2") (pinfunction "VOUT_2") (pintype "passive"))
      (node (ref "U7") (pin "5") (pinfunction "Vio_5") (pintype "passive"))
      (node (ref "U8") (pin "3") (pinfunction "V+_3") (pintype "passive"))
      (node (ref "U9") (pin "3") (pinfunction "V+_3") (pintype "passive"))
    )
    (net (code "41") (name "5V") (class "Default")
      (node (ref "C14") (pin "2") (pinfunction "2_2") (pintype "passive"))
      (node (ref "C16") (pin "2") (pinfunction "2_2") (pintype "passive"))
      (node (ref "C17") (pin "2") (pinfunction "2_2") (pintype "passive"))
      (node (ref "J4") (pin "2") (pinfunction "2_2") (pintype "passive"))
      (node (ref "J5") (pin "1") (pinfunction "1_1") (pintype "passive"))
      (node (ref "L1") (pin "2") (pinfunction "2_2") (pintype "passive"))
      (node (ref "R23") (pin "1") (pinfunction "1_1") (pintype "passive"))
      (node (ref "TP5") (pin "1") (pinfunction "1_1") (pintype "passive"))
      (node (ref "U4") (pin "5") (pinfunction "IN_5") (pintype "passive"))
      (node (ref "U5") (pin "5") (pinfunction "IN_5") (pintype "passive"))
      (node (ref "U6") (pin "3") (pinfunction "VIN_3") (pintype "passive"))
      (node (ref "U7") (pin "3") (pinfunction "Vcc_3") (pintype "passive"))
    )
    (net (code "42") (name "24V") (class "Default")
      (node (ref "C8") (pin "2") (pinfunction "2_2") (pintype "passive"))
      (node (ref "D1") (pin "2") (pinfunction "K_2") (pintype "passive"))
      (node (ref "J1") (pin "1") (pinfunction "1_1") (pintype "passive"))
      (node (ref "R16") (pin "1") (pinfunction "1_1") (pintype "passive"))
      (node (ref "R33") (pin "1") (pinfunction "1_1") (pintype "passive"))
      (node (ref "U2") (pin "3") (pinfunction "VIN_3") (pintype "passive"))
    )
    (net (code "43") (name "GND") (class "Default")
      (node (ref "C1") (pin "1") (pinfunction "1_1") (pintype "passive"))
      (node (ref "C12") (pin "1") (pinfunction "1_1") (pintype "passive"))
      (node (ref "C13") (pin "1") (pinfunction "1_1") (pintype "passive"))
      (node (ref "C14") (pin "1") (pinfunction "1_1") (pintype "passive"))
      (node (ref "C15") (pin "1") (pinfunction "1_1") (pintype "passive"))
      (node (ref "C16") (pin "1") (pinfunction "1_1") (pintype "passive"))
      (node (ref "C17") (pin "1") (pinfunction "1_1") (pintype "passive"))
      (node (ref "C18") (pin "1") (pinfunction "1_1") (pintype "passive"))
      (node (ref "C19") (pin "1") (pinfunction "1_1") (pintype "passive"))
      (node (ref "C2") (pin "1") (pinfunction "1_1") (pintype "passive"))
      (node (ref "C20") (pin "1") (pinfunction "1_1") (pintype "passive"))
      (node (ref "C21") (pin "1") (pinfunction "1_1") (pintype "passive"))
      (node (ref "C22") (pin "1") (pinfunction "1_1") (pintype "passive"))
      (node (ref "C23") (pin "1") (pinfunction "1_1") (pintype "passive"))
      (node (ref "C24") (pin "1") (pinfunction "1_1") (pintype "passive"))
      (node (ref "C25") (pin "1") (pinfunction "1_1") (pintype "passive"))
      (node (ref "C26") (pin "1") (pinfunction "1_1") (pintype "passive"))
      (node (ref "C27") (pin "1") (pinfunction "1_1") (pintype "passive"))
      (node (ref "C3") (pin "1") (pinfunction "1_1") (pintype "passive"))
      (node (ref "C4") (pin "1") (pinfunction "1_1") (pintype "passive"))
      (node (ref "C5") (pin "1") (pinfunction "1_1") (pintype "passive"))
      (node (ref "C6") (pin "1") (pinfunction "1_1") (pintype "passive"))
      (node (ref "C7") (pin "1") (pinfunction "1_1") (pintype "passive"))
      (node (ref "C8") (pin "1") (pinfunction "1_1") (pintype "passive"))
      (node (ref "C9") (pin "1") (pinfunction "1_1") (pintype "passive"))
      (node (ref "D1") (pin "1") (pinfunction "A_1") (pintype "passive"))
      (node (ref "D2") (pin "2") (pinfunction "K_2") (pintype "passive"))
      (node (ref "D3") (pin "3") (pinfunction "3_3") (pintype "passive"))
      (node (ref "J1") (pin "2") (pinfunction "2_2") (pintype "passive"))
      (node (ref "J3") (pin "3") (pinfunction "3_3") (pintype "passive"))
      (node (ref "J4") (pin "3") (pinfunction "3_3") (pintype "passive"))
      (node (ref "J5") (pin "4") (pinfunction "4_4") (pintype "passive"))
      (node (ref "J6") (pin "4") (pinfunction "4_4") (pintype "passive"))
      (node (ref "R11") (pin "1") (pinfunction "1_1") (pintype "passive"))
      (node (ref "R12") (pin "1") (pinfunction "1_1") (pintype "passive"))
      (node (ref "R13") (pin "1") (pinfunction "1_1") (pintype "passive"))
      (node (ref "R14") (pin "1") (pinfunction "1_1") (pintype "passive"))
      (node (ref "R15") (pin "2") (pinfunction "2_2") (pintype "passive"))
      (node (ref "R17") (pin "2") (pinfunction "2_2") (pintype "passive"))
      (node (ref "R22") (pin "2") (pinfunction "2_2") (pintype "passive"))
      (node (ref "R27") (pin "2") (pinfunction "2_2") (pintype "passive"))
      (node (ref "R28") (pin "2") (pinfunction "2_2") (pintype "passive"))
      (node (ref "R34") (pin "2") (pinfunction "2_2") (pintype "passive"))
      (node (ref "TP10") (pin "1") (pinfunction "1_1") (pintype "passive"))
      (node (ref "TP11") (pin "1") (pinfunction "1_1") (pintype "passive"))
      (node (ref "TP12") (pin "1") (pinfunction "1_1") (pintype "passive"))
      (node (ref "TP13") (pin "1") (pinfunction "1_1") (pintype "passive"))
      (node (ref "TP14") (pin "1") (pinfunction "1_1") (pintype "passive"))
      (node (ref "TP8") (pin "1") (pinfunction "1_1") (pintype "passive"))
      (node (ref "TP9") (pin "1") (pinfunction "1_1") (pintype "passive"))
      (node (ref "U1") (pin "23") (pinfunction "VSS_1_23") (pintype "passive"))
      (node (ref "U1") (pin "35") (pinfunction "VSS_2_35") (pintype "passive"))
      (node (ref "U1") (pin "44") (pinfunction "BOOT0_44") (pintype "passive"))
      (node (ref "U1") (pin "47") (pinfunction "VSS_3_47") (pintype "passive"))
      (node (ref "U1") (pin "8") (pinfunction "VSS_A_8") (pintype "passive"))
      (node (ref "U10") (pin "5") (pinfunction "GND_5") (pintype "passive"))
      (node (ref "U11") (pin "2") (pinfunction "GND_2") (pintype "passive"))
      (node (ref "U11") (pin "5") (pinfunction "WP_5") (pintype "passive"))
      (node (ref "U2") (pin "1") (pinfunction "GND_1") (pintype "passive"))
      (node (ref "U3") (pin "1") (pinfunction "GND_1") (pintype "passive"))
      (node (ref "U3") (pin "7") (pinfunction "GND_7") (pintype "passive"))
      (node (ref "U4") (pin "2") (pinfunction "GND_2") (pintype "passive"))
      (node (ref "U5") (pin "2") (pinfunction "GND_2") (pintype "passive"))
      (node (ref "U6") (pin "1") (pinfunction "VSS_1") (pintype "passive"))
      (node (ref "U7") (pin "2") (pinfunction "GND_2") (pintype "passive"))
      (node (ref "U7") (pin "8") (pinfunction "STB_8") (pintype "passive"))
      (node (ref "U7") (pin "9") (pinfunction "EP_9") (pintype "passive"))
      (node (ref "U8") (pin "1") (pinfunction "REF_1") (pintype "power_in"))
      (node (ref "U8") (pin "2") (pinfunction "GND_2") (pintype "power_in"))
      (node (ref "U9") (pin "1") (pinfunction "REF_1") (pintype "power_in"))
      (node (ref "U9") (pin "2") (pinfunction "GND_2") (pintype "power_in"))
    )
    (net (code "44") (name "Net-(C11-Pad2)") (class "Default")
      (node (ref "C11") (pin "2") (pinfunction "2_2") (pintype "passive"))
      (node (ref "R21") (pin "1") (pinfunction "1_1") (pintype "passive"))
      (node (ref "R23") (pin "2") (pinfunction "2_2") (pintype "passive"))
    )
    (net (code "45") (name "Net-(D2-A)") (class "Default")
      (node (ref "D2") (pin "1") (pinfunction "A_1") (pintype "passive"))
      (node (ref "R18") (pin "1") (pinfunction "1_1") (pintype "passive"))
    )
    (net (code "46") (name "Net-(J6-Pad1)") (class "Default")
      (node (ref "J6") (pin "1") (pinfunction "1_1") (pintype "passive"))
      (node (ref "R9") (pin "2") (pinfunction "2_2") (pintype "passive"))
    )
    (net (code "47") (name "Net-(J6-Pad2)") (class "Default")
      (node (ref "J6") (pin "2") (pinfunction "2_2") (pintype "passive"))
      (node (ref "R10") (pin "2") (pinfunction "2_2") (pintype "passive"))
    )
    (net (code "48") (name "Net-(R1-Pad2)") (class "Default")
      (node (ref "R1") (pin "2") (pinfunction "2_2") (pintype "passive"))
      (node (ref "TP1") (pin "1") (pinfunction "1_1") (pintype "passive"))
    )
    (net (code "49") (name "Net-(R2-Pad2)") (class "Default")
      (node (ref "R2") (pin "2") (pinfunction "2_2") (pintype "passive"))
      (node (ref "TP2") (pin "1") (pinfunction "1_1") (pintype "passive"))
    )
    (net (code "50") (name "Net-(R3-Pad2)") (class "Default")
      (node (ref "R3") (pin "2") (pinfunction "2_2") (pintype "passive"))
      (node (ref "TP3") (pin "1") (pinfunction "1_1") (pintype "passive"))
    )
    (net (code "51") (name "Net-(R4-Pad2)") (class "Default")
      (node (ref "R4") (pin "2") (pinfunction "2_2") (pintype "passive"))
      (node (ref "TP4") (pin "1") (pinfunction "1_1") (pintype "passive"))
    )
    (net (code "52") (name "Net-(U1-NRST)") (class "Default")
      (node (ref "C12") (pin "2") (pinfunction "2_2") (pintype "passive"))
      (node (ref "R26") (pin "2") (pinfunction "2_2") (pintype "passive"))
      (node (ref "U1") (pin "7") (pinfunction "NRST_7") (pintype "passive"))
    )
    (net (code "53") (name "Net-(U1-PB6)") (class "Default")
      (node (ref "R19") (pin "2") (pinfunction "2_2") (pintype "passive"))
      (node (ref "U1") (pin "42") (pinfunction "PB6_42") (pintype "passive"))
    )
    (net (code "54") (name "Net-(U1-PB7)") (class "Default")
      (node (ref "R20") (pin "2") (pinfunction "2_2") (pintype "passive"))
      (node (ref "U1") (pin "43") (pinfunction "PB7_43") (pintype "passive"))
    )
    (net (code "55") (name "Net-(U1-VDD_A)") (class "Default")
      (node (ref "C13") (pin "2") (pinfunction "2_2") (pintype "passive"))
      (node (ref "L2") (pin "2") (pinfunction "2_2") (pintype "passive"))
      (node (ref "U1") (pin "9") (pinfunction "VDD_A_9") (pintype "passive"))
    )
    (net (code "56") (name "Net-(U2-BOOT)") (class "Default")
      (node (ref "C10") (pin "1") (pinfunction "1_1") (pintype "passive"))
      (node (ref "U2") (pin "6") (pinfunction "BOOT_6") (pintype "passive"))
    )
    (net (code "57") (name "Net-(U2-FB)") (class "Default")
      (node (ref "C11") (pin "1") (pinfunction "1_1") (pintype "passive"))
      (node (ref "R21") (pin "2") (pinfunction "2_2") (pintype "passive"))
      (node (ref "R22") (pin "1") (pinfunction "1_1") (pintype "passive"))
      (node (ref "U2") (pin "4") (pinfunction "FB_4") (pintype "passive"))
    )
    (net (code "58") (name "Net-(U2-SW)") (class "Default")
      (node (ref "C10") (pin "2") (pinfunction "2_2") (pintype "passive"))
      (node (ref "L1") (pin "1") (pinfunction "1_1") (pintype "passive"))
      (node (ref "U2") (pin "2") (pinfunction "SW_2") (pintype "passive"))
    )
    (net (code "59") (name "Net-(U4-ISET)") (class "Default")
      (node (ref "R27") (pin "1") (pinfunction "1_1") (pintype "passive"))
      (node (ref "U4") (pin "3") (pinfunction "ISET_3") (pintype "passive"))
    )
    (net (code "60") (name "Net-(U4-OUT)") (class "Default")
      (node (ref "R29") (pin "2") (pinfunction "2_2") (pintype "passive"))
      (node (ref "U4") (pin "1") (pinfunction "OUT_1") (pintype "passive"))
      (node (ref "U8") (pin "4") (pinfunction "+_4") (pintype "passive"))
    )
    (net (code "61") (name "Net-(U5-ISET)") (class "Default")
      (node (ref "R28") (pin "1") (pinfunction "1_1") (pintype "passive"))
      (node (ref "U5") (pin "3") (pinfunction "ISET_3") (pintype "passive"))
    )
    (net (code "62") (name "Net-(U5-OUT)") (class "Default")
      (node (ref "R30") (pin "2") (pinfunction "2_2") (pintype "passive"))
      (node (ref "U5") (pin "1") (pinfunction "OUT_1") (pintype "passive"))
      (node (ref "U9") (pin "4") (pinfunction "+_4") (pintype "passive"))
    )
    (net (code "63") (name "Net-(U8-OUT)") (class "Default")
      (node (ref "R31") (pin "2") (pinfunction "2_2") (pintype "passive"))
      (node (ref "U8") (pin "6") (pinfunction "OUT_6") (pintype "passive"))
    )
    (net (code "64") (name "Net-(U9--)") (class "Default")
      (node (ref "R30") (pin "1") (pinfunction "1_1") (pintype "passive"))
      (node (ref "TP30") (pin "1") (pinfunction "1_1") (pintype "passive"))
      (node (ref "U9") (pin "5") (pinfunction "-_5") (pintype "passive"))
    )
    (net (code "65") (name "Net-(U9-OUT)") (class "Default")
      (node (ref "R32") (pin "2") (pinfunction "2_2") (pintype "passive"))
      (node (ref "U9") (pin "6") (pinfunction "OUT_6") (pintype "passive"))
    )
    (net (code "66") (name "SPWR") (class "Default")
      (node (ref "J6") (pin "3") (pinfunction "3_3") (pintype "passive"))
      (node (ref "R29") (pin "1") (pinfunction "1_1") (pintype "passive"))
      (node (ref "U8") (pin "5") (pinfunction "-_5") (pintype "passive"))
    )
  )
)
